# foc.net
KiCad netlist of a schematic drawn in Altium Designer
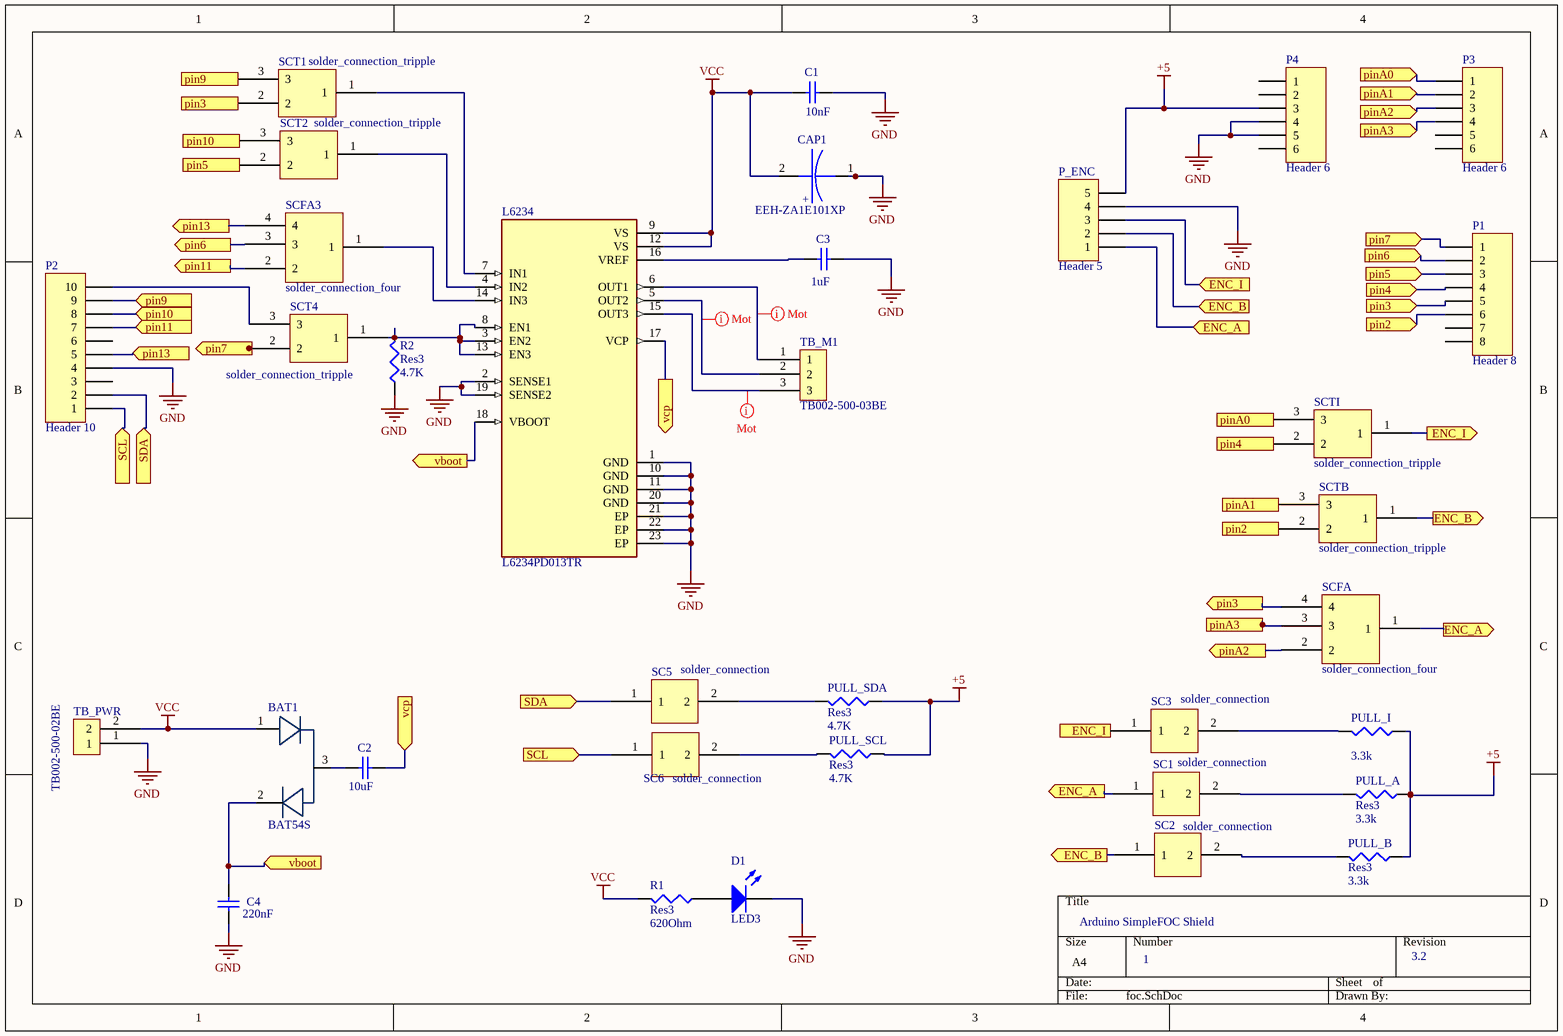
[diagram p0: foc.SchDoc]

(export (version "E")
  (design (tool "Eeschema 10.0.6"))
  (components
    (comp (ref "BAT1") (value "BAT54S") (footprint "BAT54s") (libsource (lib "ArduinoFOC") (part "BAT54S")))
    (comp (ref "C1")
      (value "10nF")
      (footprint "C1206")
      (description "Capacitor (Semiconductor SIM Model)")
      (fields (field (name "Comment") "Cap Semi") (field (name "PUBLISHER") "Altium Limited"))
      (libsource (lib "Miscellaneous Devices") (part "Cap Semi"))
    )
    (comp (ref "C2")
      (value "10uF")
      (footprint "C1206")
      (description "Capacitor (Semiconductor SIM Model)")
      (fields (field (name "Comment") "Cap Semi") (field (name "PUBLISHER") "Altium Limited"))
      (libsource (lib "Miscellaneous Devices") (part "Cap Semi"))
    )
    (comp (ref "C3")
      (value "1uF")
      (footprint "C1206")
      (description "Capacitor (Semiconductor SIM Model)")
      (fields (field (name "Comment") "Cap Semi") (field (name "PUBLISHER") "Altium Limited"))
      (libsource (lib "Miscellaneous Devices") (part "Cap Semi"))
    )
    (comp (ref "C4")
      (value "220nF")
      (footprint "C1206")
      (description "Capacitor (Semiconductor SIM Model)")
      (fields (field (name "Comment") "Cap Semi") (field (name "PUBLISHER") "Altium Limited"))
      (libsource (lib "Miscellaneous Devices") (part "Cap Semi"))
    )
    (comp (ref "CAP1")
      (value "EEH-ZA1E101XP")
      (footprint "EEH-ZA1E101XP")
      (libsource (lib "ArduinoFOC") (part "EEH-ZA1E101XP"))
    )
    (comp (ref "D1")
      (value "LED3")
      (footprint "3.5X2.8X1.9")
      (description "Typical BLUE SiC LED")
      (fields (field (name "PUBLISHER") "Altium Limited"))
      (libsource (lib "Miscellaneous Devices") (part "LED3"))
    )
    (comp (ref "L6234")
      (value "L6234PD013TR")
      (footprint "SOIC127P1420X360-21N")
      (description "Motor Driver BiCDMOS Parallel PowerSO-20")
      (fields (field (name "MF") "STMicroelectronics") (field (name "DIGI-KEY_PART_NUMBER") "497-5352-1-ND"))
      (libsource (lib "SnapEDAsch") (part "L6234PD013TR"))
    )
    (comp (ref "P1")
      (value "Header 8")
      (footprint "HDR1X8")
      (description "Header, 8-Pin")
      (fields (field (name "PUBLISHER") "Altium Limited"))
      (libsource (lib "Miscellaneous Connectors") (part "Header 8"))
    )
    (comp (ref "P2")
      (value "Header 10")
      (footprint "HDR1X10")
      (description "Header, 10-Pin")
      (fields (field (name "PUBLISHER") "Altium Limited"))
      (libsource (lib "Miscellaneous Connectors") (part "Header 10"))
    )
    (comp (ref "P3")
      (value "Header 6")
      (footprint "HDR1X6")
      (description "Header, 6-Pin")
      (fields (field (name "PUBLISHER") "Altium Limited"))
      (libsource (lib "Miscellaneous Connectors") (part "Header 6"))
    )
    (comp (ref "P4")
      (value "Header 6")
      (footprint "HDR1X6")
      (description "Header, 6-Pin")
      (fields (field (name "PUBLISHER") "Altium Limited"))
      (libsource (lib "Miscellaneous Connectors") (part "Header 6"))
    )
    (comp (ref "PULL_A")
      (value "Res3")
      (footprint "14-1210")
      (description "Resistor")
      (fields (field (name "ALTIUM_VALUE") "3.3k") (field (name "PUBLISHER") "Altium Limited"))
      (libsource (lib "Miscellaneous Devices") (part "Res3"))
    )
    (comp (ref "PULL_B")
      (value "Res3")
      (footprint "14-1210")
      (description "Resistor")
      (fields (field (name "ALTIUM_VALUE") "3.3k") (field (name "PUBLISHER") "Altium Limited"))
      (libsource (lib "Miscellaneous Devices") (part "Res3"))
    )
    (comp (ref "PULL_I")
      (value "3.3k")
      (footprint "14-1210")
      (description "Resistor")
      (fields (field (name "Comment") "Res3") (field (name "PUBLISHER") "Altium Limited"))
      (libsource (lib "Miscellaneous Devices") (part "Res3"))
    )
    (comp (ref "PULL_SCL")
      (value "Res3")
      (footprint "14-1210")
      (description "Resistor")
      (fields (field (name "ALTIUM_VALUE") "4.7K") (field (name "PUBLISHER") "Altium Limited"))
      (libsource (lib "Miscellaneous Devices") (part "Res3"))
    )
    (comp (ref "PULL_SDA")
      (value "Res3")
      (footprint "14-1210")
      (description "Resistor")
      (fields (field (name "ALTIUM_VALUE") "4.7K") (field (name "PUBLISHER") "Altium Limited"))
      (libsource (lib "Miscellaneous Devices") (part "Res3"))
    )
    (comp (ref "P_ENC")
      (value "Header 5")
      (footprint "HDR1X5")
      (description "Header, 5-Pin")
      (fields (field (name "PUBLISHER") "Altium Limited"))
      (libsource (lib "Miscellaneous Connectors") (part "Header 5"))
    )
    (comp (ref "R1")
      (value "Res3")
      (footprint "14-1210")
      (description "Resistor")
      (fields (field (name "ALTIUM_VALUE") "620Ohm") (field (name "PUBLISHER") "Altium Limited"))
      (libsource (lib "Miscellaneous Devices") (part "Res3"))
    )
    (comp (ref "R2")
      (value "Res3")
      (footprint "14-1210")
      (description "Resistor")
      (fields (field (name "ALTIUM_VALUE") "4.7K") (field (name "PUBLISHER") "Altium Limited"))
      (libsource (lib "Miscellaneous Devices") (part "Res3"))
    )
    (comp (ref "SC1")
      (value "solder_connection")
      (footprint "solder_connection")
      (libsource (lib "ArduinoFOC") (part "solder_connection"))
    )
    (comp (ref "SC2")
      (value "solder_connection")
      (footprint "solder_connection")
      (libsource (lib "ArduinoFOC") (part "solder_connection"))
    )
    (comp (ref "SC3")
      (value "solder_connection")
      (footprint "solder_connection")
      (libsource (lib "ArduinoFOC") (part "solder_connection"))
    )
    (comp (ref "SC5")
      (value "solder_connection")
      (footprint "solder_connection")
      (libsource (lib "ArduinoFOC") (part "solder_connection"))
    )
    (comp (ref "SC6")
      (value "solder_connection")
      (footprint "solder_connection")
      (libsource (lib "ArduinoFOC") (part "solder_connection"))
    )
    (comp (ref "SCFA")
      (value "solder_connection_four")
      (footprint "solder_connection_four")
      (libsource (lib "ArduinoFOC") (part "solder_connection_four"))
    )
    (comp (ref "SCFA3")
      (value "solder_connection_four")
      (footprint "solder_connection_four")
      (libsource (lib "ArduinoFOC") (part "solder_connection_four"))
    )
    (comp (ref "SCT1")
      (value "solder_connection_tripple")
      (footprint "solder_connection_tripple")
      (libsource (lib "ArduinoFOC") (part "solder_connection_tripple"))
    )
    (comp (ref "SCT2")
      (value "solder_connection_tripple")
      (footprint "solder_connection_tripple")
      (libsource (lib "ArduinoFOC") (part "solder_connection_tripple"))
    )
    (comp (ref "SCT4")
      (value "solder_connection_tripple")
      (footprint "solder_connection_tripple")
      (libsource (lib "ArduinoFOC") (part "solder_connection_tripple"))
    )
    (comp (ref "SCTB")
      (value "solder_connection_tripple")
      (footprint "solder_connection_tripple")
      (libsource (lib "ArduinoFOC") (part "solder_connection_tripple"))
    )
    (comp (ref "SCTI")
      (value "solder_connection_tripple")
      (footprint "solder_connection_tripple")
      (libsource (lib "ArduinoFOC") (part "solder_connection_tripple"))
    )
    (comp (ref "TB_M1")
      (value "TB002-500-03BE")
      (footprint "TB002-500-03BE")
      (libsource (lib "ArduinoFOC") (part "TB002-500-03BE"))
    )
    (comp (ref "TB_PWR")
      (value "TB002-500-02BE")
      (footprint "TB002-500-02BE")
      (libsource (lib "ArduinoFOC") (part "TB002-500-02BE"))
    )
  )
  (nets
    (net (code "1") (name "+5") (class "Default")
      (node (ref "P4") (pin "3") (pinfunction "3_3") (pintype "passive"))
      (node (ref "PULL_A") (pin "1") (pinfunction "1_1") (pintype "passive"))
      (node (ref "PULL_B") (pin "1") (pinfunction "1_1") (pintype "passive"))
      (node (ref "PULL_I") (pin "1") (pinfunction "1_1") (pintype "passive"))
      (node (ref "PULL_SCL") (pin "1") (pinfunction "1_1") (pintype "passive"))
      (node (ref "PULL_SDA") (pin "1") (pinfunction "1_1") (pintype "passive"))
      (node (ref "P_ENC") (pin "5") (pinfunction "5_5") (pintype "passive"))
    )
    (net (code "2") (name "/ENC_A") (class "Default")
      (node (ref "P_ENC") (pin "1") (pinfunction "1_1") (pintype "passive"))
      (node (ref "SC1") (pin "1") (pinfunction "1_1") (pintype "passive"))
      (node (ref "SCFA") (pin "1") (pinfunction "1_1") (pintype "passive"))
    )
    (net (code "3") (name "/ENC_B") (class "Default")
      (node (ref "P_ENC") (pin "2") (pinfunction "2_2") (pintype "passive"))
      (node (ref "SC2") (pin "1") (pinfunction "1_1") (pintype "passive"))
      (node (ref "SCTB") (pin "1") (pinfunction "1_1") (pintype "passive"))
    )
    (net (code "4") (name "/ENC_I") (class "Default")
      (node (ref "P_ENC") (pin "3") (pinfunction "3_3") (pintype "passive"))
      (node (ref "SC3") (pin "1") (pinfunction "1_1") (pintype "passive"))
      (node (ref "SCTI") (pin "1") (pinfunction "1_1") (pintype "passive"))
    )
    (net (code "5") (name "/SCL") (class "Default")
      (node (ref "P2") (pin "1") (pinfunction "1_1") (pintype "passive"))
      (node (ref "SC6") (pin "1") (pinfunction "1_1") (pintype "passive"))
    )
    (net (code "6") (name "/SDA") (class "Default")
      (node (ref "P2") (pin "2") (pinfunction "2_2") (pintype "passive"))
      (node (ref "SC5") (pin "1") (pinfunction "1_1") (pintype "passive"))
    )
    (net (code "7") (name "/pin2") (class "Default")
      (node (ref "P1") (pin "6") (pinfunction "6_6") (pintype "passive"))
      (node (ref "SCTB") (pin "2") (pinfunction "2_2") (pintype "passive"))
    )
    (net (code "8") (name "/pin3") (class "Default")
      (node (ref "P1") (pin "5") (pinfunction "5_5") (pintype "passive"))
      (node (ref "SCFA") (pin "4") (pinfunction "4_4") (pintype "passive"))
      (node (ref "SCT1") (pin "2") (pinfunction "2_2") (pintype "passive"))
    )
    (net (code "9") (name "/pin4") (class "Default")
      (node (ref "P1") (pin "4") (pinfunction "4_4") (pintype "passive"))
      (node (ref "SCTI") (pin "2") (pinfunction "2_2") (pintype "passive"))
    )
    (net (code "10") (name "/pin5") (class "Default")
      (node (ref "P1") (pin "3") (pinfunction "3_3") (pintype "passive"))
      (node (ref "SCT2") (pin "2") (pinfunction "2_2") (pintype "passive"))
    )
    (net (code "11") (name "/pin6") (class "Default")
      (node (ref "P1") (pin "2") (pinfunction "2_2") (pintype "passive"))
      (node (ref "SCFA3") (pin "3") (pinfunction "3_3") (pintype "passive"))
    )
    (net (code "12") (name "/pin7") (class "Default")
      (node (ref "P1") (pin "1") (pinfunction "1_1") (pintype "passive"))
      (node (ref "SCT4") (pin "2") (pinfunction "2_2") (pintype "passive"))
    )
    (net (code "13") (name "/pin9") (class "Default")
      (node (ref "P2") (pin "9") (pinfunction "9_9") (pintype "passive"))
      (node (ref "SCT1") (pin "3") (pinfunction "3_3") (pintype "passive"))
    )
    (net (code "14") (name "/pin10") (class "Default")
      (node (ref "P2") (pin "8") (pinfunction "8_8") (pintype "passive"))
      (node (ref "SCT2") (pin "3") (pinfunction "3_3") (pintype "passive"))
    )
    (net (code "15") (name "/pin11") (class "Default")
      (node (ref "P2") (pin "7") (pinfunction "7_7") (pintype "passive"))
      (node (ref "SCFA3") (pin "2") (pinfunction "2_2") (pintype "passive"))
    )
    (net (code "16") (name "/pin13") (class "Default")
      (node (ref "P2") (pin "5") (pinfunction "5_5") (pintype "passive"))
      (node (ref "SCFA3") (pin "4") (pinfunction "4_4") (pintype "passive"))
    )
    (net (code "17") (name "/pinA0") (class "Default")
      (node (ref "P3") (pin "1") (pinfunction "1_1") (pintype "passive"))
      (node (ref "SCTI") (pin "3") (pinfunction "3_3") (pintype "passive"))
    )
    (net (code "18") (name "/pinA1") (class "Default")
      (node (ref "P3") (pin "2") (pinfunction "2_2") (pintype "passive"))
      (node (ref "SCTB") (pin "3") (pinfunction "3_3") (pintype "passive"))
    )
    (net (code "19") (name "/pinA2") (class "Default")
      (node (ref "P3") (pin "3") (pinfunction "3_3") (pintype "passive"))
      (node (ref "SCFA") (pin "2") (pinfunction "2_2") (pintype "passive"))
    )
    (net (code "20") (name "/pinA3") (class "Default")
      (node (ref "P3") (pin "4") (pinfunction "4_4") (pintype "passive"))
      (node (ref "SCFA") (pin "3") (pinfunction "3_3") (pintype "passive"))
    )
    (net (code "21") (name "/vboot") (class "Default")
      (node (ref "BAT1") (pin "2") (pinfunction "2_2") (pintype "passive"))
      (node (ref "C4") (pin "2") (pinfunction "2_2") (pintype "passive"))
      (node (ref "L6234") (pin "18") (pinfunction "VBOOT_18") (pintype "input"))
    )
    (net (code "22") (name "/vcp") (class "Default")
      (node (ref "C2") (pin "2") (pinfunction "2_2") (pintype "passive"))
      (node (ref "L6234") (pin "17") (pinfunction "VCP_17") (pintype "output"))
    )
    (net (code "23") (name "GND") (class "Default")
      (node (ref "C1") (pin "2") (pinfunction "2_2") (pintype "passive"))
      (node (ref "C3") (pin "2") (pinfunction "2_2") (pintype "passive"))
      (node (ref "C4") (pin "1") (pinfunction "1_1") (pintype "passive"))
      (node (ref "CAP1") (pin "1") (pinfunction "1_1") (pintype "passive"))
      (node (ref "D1") (pin "2") (pinfunction "K_2") (pintype "passive"))
      (node (ref "L6234") (pin "1") (pinfunction "GND_1") (pintype "power_in"))
      (node (ref "L6234") (pin "10") (pinfunction "GND_10") (pintype "power_in"))
      (node (ref "L6234") (pin "11") (pinfunction "GND_11") (pintype "power_in"))
      (node (ref "L6234") (pin "19") (pinfunction "SENSE2_19") (pintype "input"))
      (node (ref "L6234") (pin "2") (pinfunction "SENSE1_2") (pintype "input"))
      (node (ref "L6234") (pin "20") (pinfunction "GND_20") (pintype "power_in"))
      (node (ref "L6234") (pin "21") (pinfunction "EP_21") (pintype "power_in"))
      (node (ref "L6234") (pin "22") (pinfunction "EP_22") (pintype "power_in"))
      (node (ref "L6234") (pin "23") (pinfunction "EP_23") (pintype "power_in"))
      (node (ref "P2") (pin "4") (pinfunction "4_4") (pintype "passive"))
      (node (ref "P4") (pin "4") (pinfunction "4_4") (pintype "passive"))
      (node (ref "P4") (pin "5") (pinfunction "5_5") (pintype "passive"))
      (node (ref "P_ENC") (pin "4") (pinfunction "4_4") (pintype "passive"))
      (node (ref "R2") (pin "1") (pinfunction "1_1") (pintype "passive"))
      (node (ref "TB_PWR") (pin "1") (pinfunction "1_1") (pintype "passive"))
    )
    (net (code "24") (name "Net-(BAT1-Pad3)") (class "Default")
      (node (ref "BAT1") (pin "3") (pinfunction "3_3") (pintype "passive"))
      (node (ref "C2") (pin "1") (pinfunction "1_1") (pintype "passive"))
    )
    (net (code "25") (name "Net-(D1-A)") (class "Default")
      (node (ref "D1") (pin "1") (pinfunction "A_1") (pintype "passive"))
      (node (ref "R1") (pin "1") (pinfunction "1_1") (pintype "passive"))
    )
    (net (code "26") (name "Net-(L6234-EN1)") (class "Default")
      (node (ref "L6234") (pin "13") (pinfunction "EN3_13") (pintype "input"))
      (node (ref "L6234") (pin "3") (pinfunction "EN2_3") (pintype "input"))
      (node (ref "L6234") (pin "8") (pinfunction "EN1_8") (pintype "input"))
      (node (ref "R2") (pin "2") (pinfunction "2_2") (pintype "passive"))
      (node (ref "SCT4") (pin "1") (pinfunction "1_1") (pintype "passive"))
    )
    (net (code "27") (name "Net-(L6234-IN1)") (class "Default")
      (node (ref "L6234") (pin "7") (pinfunction "IN1_7") (pintype "input"))
      (node (ref "SCT1") (pin "1") (pinfunction "1_1") (pintype "passive"))
    )
    (net (code "28") (name "Net-(L6234-IN2)") (class "Default")
      (node (ref "L6234") (pin "4") (pinfunction "IN2_4") (pintype "input"))
      (node (ref "SCT2") (pin "1") (pinfunction "1_1") (pintype "passive"))
    )
    (net (code "29") (name "Net-(L6234-IN3)") (class "Default")
      (node (ref "L6234") (pin "14") (pinfunction "IN3_14") (pintype "input"))
      (node (ref "SCFA3") (pin "1") (pinfunction "1_1") (pintype "passive"))
    )
    (net (code "30") (name "Net-(L6234-OUT1)") (class "Default")
      (node (ref "L6234") (pin "6") (pinfunction "OUT1_6") (pintype "output"))
      (node (ref "TB_M1") (pin "1") (pinfunction "1_1") (pintype "passive"))
    )
    (net (code "31") (name "Net-(L6234-OUT2)") (class "Default")
      (node (ref "L6234") (pin "5") (pinfunction "OUT2_5") (pintype "output"))
      (node (ref "TB_M1") (pin "2") (pinfunction "2_2") (pintype "passive"))
    )
    (net (code "32") (name "Net-(L6234-OUT3)") (class "Default")
      (node (ref "L6234") (pin "15") (pinfunction "OUT3_15") (pintype "output"))
      (node (ref "TB_M1") (pin "3") (pinfunction "3_3") (pintype "passive"))
    )
    (net (code "33") (name "Net-(L6234-VREF)") (class "Default")
      (node (ref "C3") (pin "1") (pinfunction "1_1") (pintype "passive"))
      (node (ref "L6234") (pin "16") (pinfunction "VREF_16") (pintype "power_in"))
    )
    (net (code "34") (name "Net-(P2-Pad10)") (class "Default")
      (node (ref "P2") (pin "10") (pinfunction "10_10") (pintype "passive"))
      (node (ref "SCT4") (pin "3") (pinfunction "3_3") (pintype "passive"))
    )
    (net (code "35") (name "Net-(PULL_A-Pad2)") (class "Default")
      (node (ref "PULL_A") (pin "2") (pinfunction "2_2") (pintype "passive"))
      (node (ref "SC1") (pin "2") (pinfunction "2_2") (pintype "passive"))
    )
    (net (code "36") (name "Net-(PULL_B-Pad2)") (class "Default")
      (node (ref "PULL_B") (pin "2") (pinfunction "2_2") (pintype "passive"))
      (node (ref "SC2") (pin "2") (pinfunction "2_2") (pintype "passive"))
    )
    (net (code "37") (name "Net-(PULL_I-Pad2)") (class "Default")
      (node (ref "PULL_I") (pin "2") (pinfunction "2_2") (pintype "passive"))
      (node (ref "SC3") (pin "2") (pinfunction "2_2") (pintype "passive"))
    )
    (net (code "38") (name "Net-(PULL_SCL-Pad2)") (class "Default")
      (node (ref "PULL_SCL") (pin "2") (pinfunction "2_2") (pintype "passive"))
      (node (ref "SC6") (pin "2") (pinfunction "2_2") (pintype "passive"))
    )
    (net (code "39") (name "Net-(PULL_SDA-Pad2)") (class "Default")
      (node (ref "PULL_SDA") (pin "2") (pinfunction "2_2") (pintype "passive"))
      (node (ref "SC5") (pin "2") (pinfunction "2_2") (pintype "passive"))
    )
    (net (code "40") (name "VCC") (class "Default")
      (node (ref "BAT1") (pin "1") (pinfunction "1_1") (pintype "passive"))
      (node (ref "C1") (pin "1") (pinfunction "1_1") (pintype "passive"))
      (node (ref "CAP1") (pin "2") (pinfunction "+_2") (pintype "passive"))
      (node (ref "L6234") (pin "12") (pinfunction "VS_12") (pintype "power_in"))
      (node (ref "L6234") (pin "9") (pinfunction "VS_9") (pintype "power_in"))
      (node (ref "R1") (pin "2") (pinfunction "2_2") (pintype "passive"))
      (node (ref "TB_PWR") (pin "2") (pinfunction "2_2") (pintype "passive"))
    )
    (net (code "41") (name "unconnected-(P1-Pad7)") (class "Default")
      (node (ref "P1") (pin "7") (pinfunction "7_7") (pintype "passive"))
    )
    (net (code "42") (name "unconnected-(P1-Pad8)") (class "Default")
      (node (ref "P1") (pin "8") (pinfunction "8_8") (pintype "passive"))
    )
    (net (code "43") (name "unconnected-(P2-Pad3)") (class "Default")
      (node (ref "P2") (pin "3") (pinfunction "3_3") (pintype "passive"))
    )
    (net (code "44") (name "unconnected-(P2-Pad6)") (class "Default")
      (node (ref "P2") (pin "6") (pinfunction "6_6") (pintype "passive"))
    )
    (net (code "45") (name "unconnected-(P3-Pad5)") (class "Default")
      (node (ref "P3") (pin "5") (pinfunction "5_5") (pintype "passive"))
    )
    (net (code "46") (name "unconnected-(P3-Pad6)") (class "Default")
      (node (ref "P3") (pin "6") (pinfunction "6_6") (pintype "passive"))
    )
    (net (code "47") (name "unconnected-(P4-Pad1)") (class "Default")
      (node (ref "P4") (pin "1") (pinfunction "1_1") (pintype "passive"))
    )
    (net (code "48") (name "unconnected-(P4-Pad2)") (class "Default")
      (node (ref "P4") (pin "2") (pinfunction "2_2") (pintype "passive"))
    )
    (net (code "49") (name "unconnected-(P4-Pad6)") (class "Default")
      (node (ref "P4") (pin "6") (pinfunction "6_6") (pintype "passive"))
    )
  )
)
